# New_Project_2025-06-11_12-14-33.net
KiCad netlist of a schematic drawn in EasyEDA Pro
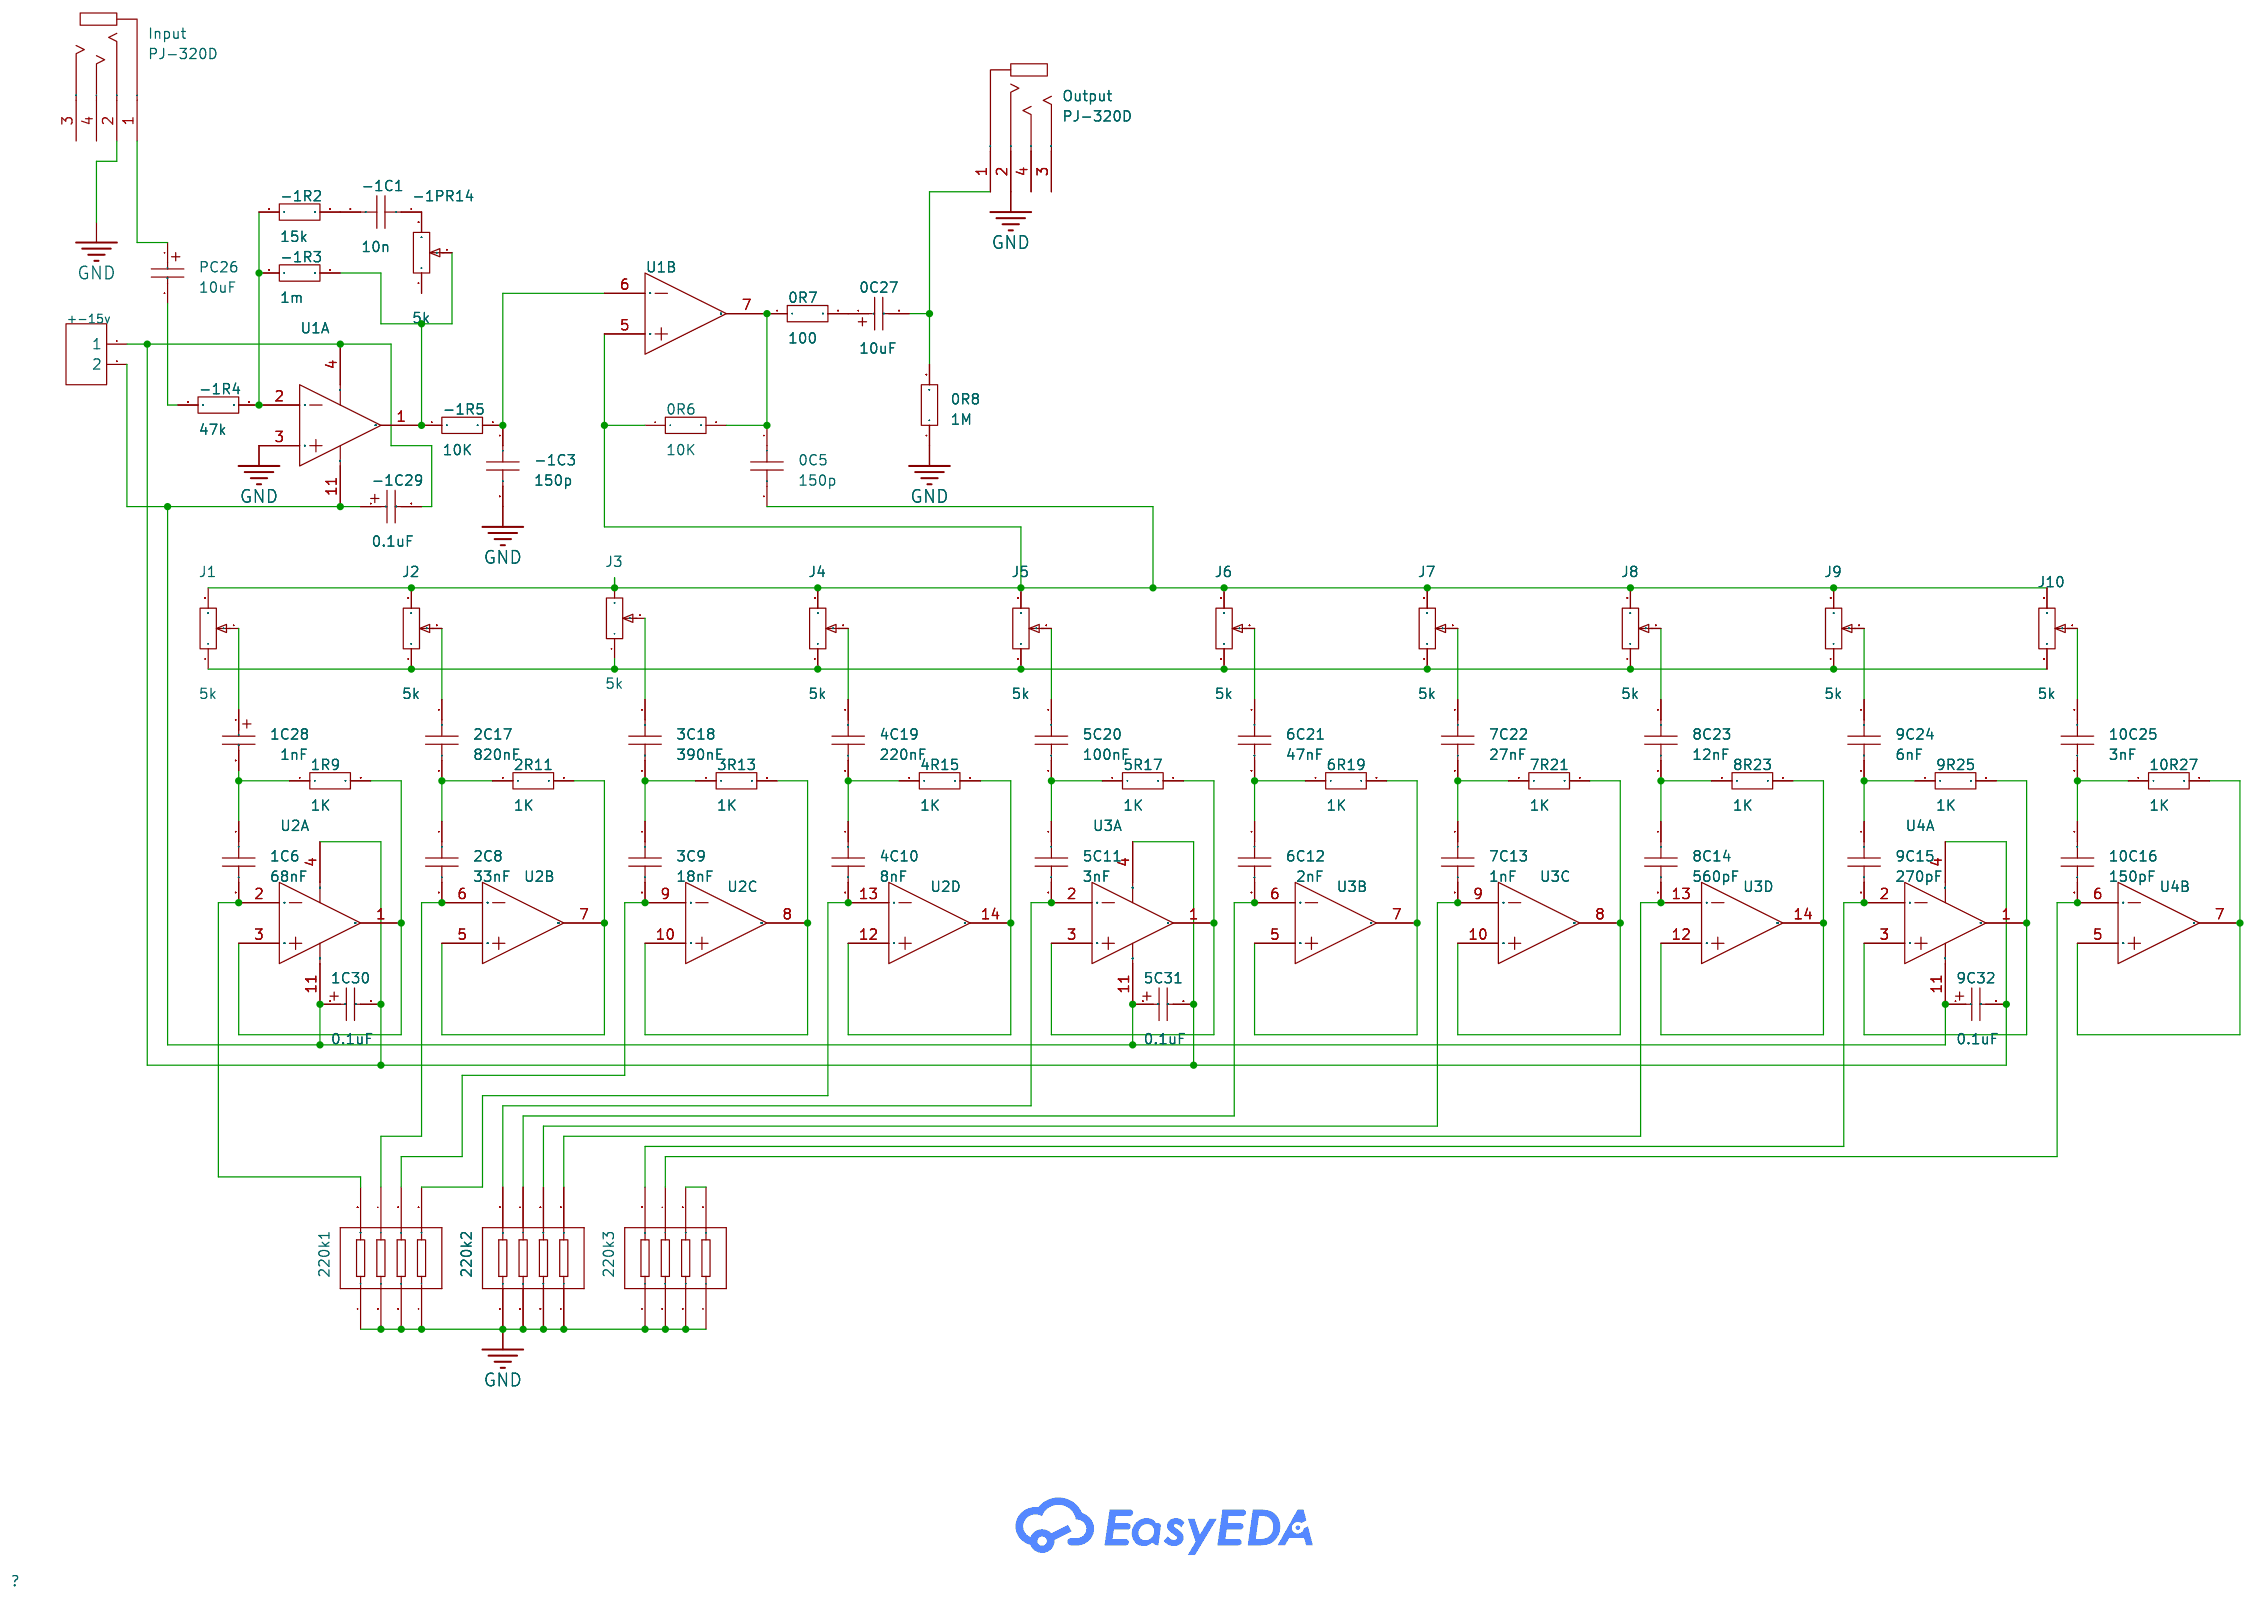
[diagram p0: schematic sheet]

(export (version "E")
  (design (tool "Eeschema 10.0.6"))
  (components
    (comp (ref "+-15v")
      (value "~")
      (footprint "easyedapro:HDR-TH_2P-P2.54-V-F")
      (libsource (lib "easyedapro") (part "Header-Female-2.54_1x2"))
    )
    (comp (ref "-1C1")
      (value "10n")
      (footprint "easyedapro:C0603")
      (libsource (lib "easyedapro") (part "CAP"))
    )
    (comp (ref "-1C3")
      (value "150p")
      (footprint "easyedapro:C0603")
      (libsource (lib "easyedapro") (part "CAP"))
    )
    (comp (ref "-1C29")
      (value "0.1uF")
      (footprint "easyedapro:CAP-SMD_BD3.0-L3.3-W3.3-RD")
      (libsource (lib "easyedapro") (part "C_Ele_SMD"))
    )
    (comp (ref "-1PR14")
      (value "5k")
      (footprint "easyedapro:RES-ADJ-TH_3P-L9.5-W9.5-P2.54-BR-BS")
      (libsource (lib "easyedapro") (part "3386P-1-103LF"))
    )
    (comp (ref "-1R2")
      (value "15k")
      (footprint "easyedapro:RES-TH_BD1.8-L3.2-P7.20-D0.4")
      (libsource (lib "easyedapro") (part "Res"))
    )
    (comp (ref "-1R3")
      (value "1m")
      (footprint "easyedapro:RES-TH_BD1.8-L3.2-P7.20-D0.4")
      (libsource (lib "easyedapro") (part "Res"))
    )
    (comp (ref "-1R4")
      (value "47k")
      (footprint "easyedapro:RES-TH_BD1.8-L3.2-P7.20-D0.4")
      (libsource (lib "easyedapro") (part "Res"))
    )
    (comp (ref "-1R5")
      (value "10K")
      (footprint "easyedapro:RES-TH_BD1.8-L3.2-P7.20-D0.4")
      (libsource (lib "easyedapro") (part "Res"))
    )
    (comp (ref "0C5")
      (value "150p")
      (footprint "easyedapro:C0603")
      (libsource (lib "easyedapro") (part "CAP"))
    )
    (comp (ref "0C27")
      (value "10uF")
      (footprint "easyedapro:CAP-SMD_BD3.0-L3.3-W3.3-RD")
      (libsource (lib "easyedapro") (part "C_Ele_SMD"))
    )
    (comp (ref "0R6")
      (value "10K")
      (footprint "easyedapro:RES-TH_BD1.8-L3.2-P7.20-D0.4")
      (libsource (lib "easyedapro") (part "Res"))
    )
    (comp (ref "0R7")
      (value "100")
      (footprint "easyedapro:RES-TH_BD1.8-L3.2-P7.20-D0.4")
      (libsource (lib "easyedapro") (part "Res"))
    )
    (comp (ref "0R8")
      (value "1M")
      (footprint "easyedapro:RES-TH_BD1.8-L3.2-P7.20-D0.4")
      (libsource (lib "easyedapro") (part "Res"))
    )
    (comp (ref "1C6")
      (value "68nF")
      (footprint "easyedapro:C0603")
      (libsource (lib "easyedapro") (part "CAP"))
    )
    (comp (ref "1C28")
      (value "1nF")
      (footprint "easyedapro:CAP-SMD_BD3.0-L3.3-W3.3-RD")
      (libsource (lib "easyedapro") (part "C_Ele_SMD"))
    )
    (comp (ref "1C30")
      (value "0.1uF")
      (footprint "easyedapro:CAP-SMD_BD3.0-L3.3-W3.3-RD")
      (libsource (lib "easyedapro") (part "C_Ele_SMD"))
    )
    (comp (ref "1R9")
      (value "1K")
      (footprint "easyedapro:RES-TH_BD1.8-L3.2-P7.20-D0.4")
      (libsource (lib "easyedapro") (part "Res"))
    )
    (comp (ref "2C8")
      (value "33nF")
      (footprint "easyedapro:C0603")
      (libsource (lib "easyedapro") (part "CAP"))
    )
    (comp (ref "2C17")
      (value "820nF")
      (footprint "easyedapro:C0603")
      (libsource (lib "easyedapro") (part "CAP"))
    )
    (comp (ref "2R11")
      (value "1K")
      (footprint "easyedapro:RES-TH_BD1.8-L3.2-P7.20-D0.4")
      (libsource (lib "easyedapro") (part "Res"))
    )
    (comp (ref "3C9")
      (value "18nF")
      (footprint "easyedapro:C0603")
      (libsource (lib "easyedapro") (part "CAP"))
    )
    (comp (ref "3C18")
      (value "390nF")
      (footprint "easyedapro:C0603")
      (libsource (lib "easyedapro") (part "CAP"))
    )
    (comp (ref "3R13")
      (value "1K")
      (footprint "easyedapro:RES-TH_BD1.8-L3.2-P7.20-D0.4")
      (libsource (lib "easyedapro") (part "Res"))
    )
    (comp (ref "4C10")
      (value "8nF")
      (footprint "easyedapro:C0603")
      (libsource (lib "easyedapro") (part "CAP"))
    )
    (comp (ref "4C19")
      (value "220nF")
      (footprint "easyedapro:C0603")
      (libsource (lib "easyedapro") (part "CAP"))
    )
    (comp (ref "4R15")
      (value "1K")
      (footprint "easyedapro:RES-TH_BD1.8-L3.2-P7.20-D0.4")
      (libsource (lib "easyedapro") (part "Res"))
    )
    (comp (ref "5C11")
      (value "3nF")
      (footprint "easyedapro:C0603")
      (libsource (lib "easyedapro") (part "CAP"))
    )
    (comp (ref "5C20")
      (value "100nF")
      (footprint "easyedapro:C0603")
      (libsource (lib "easyedapro") (part "CAP"))
    )
    (comp (ref "5C31")
      (value "0.1uF")
      (footprint "easyedapro:CAP-SMD_BD3.0-L3.3-W3.3-RD")
      (libsource (lib "easyedapro") (part "C_Ele_SMD"))
    )
    (comp (ref "5R17")
      (value "1K")
      (footprint "easyedapro:RES-TH_BD1.8-L3.2-P7.20-D0.4")
      (libsource (lib "easyedapro") (part "Res"))
    )
    (comp (ref "6C12")
      (value "2nF")
      (footprint "easyedapro:C0603")
      (libsource (lib "easyedapro") (part "CAP"))
    )
    (comp (ref "6C21")
      (value "47nF")
      (footprint "easyedapro:C0603")
      (libsource (lib "easyedapro") (part "CAP"))
    )
    (comp (ref "6R19")
      (value "1K")
      (footprint "easyedapro:RES-TH_BD1.8-L3.2-P7.20-D0.4")
      (libsource (lib "easyedapro") (part "Res"))
    )
    (comp (ref "7C13")
      (value "1nF")
      (footprint "easyedapro:C0603")
      (libsource (lib "easyedapro") (part "CAP"))
    )
    (comp (ref "7C22")
      (value "27nF")
      (footprint "easyedapro:C0603")
      (libsource (lib "easyedapro") (part "CAP"))
    )
    (comp (ref "7R21")
      (value "1K")
      (footprint "easyedapro:RES-TH_BD1.8-L3.2-P7.20-D0.4")
      (libsource (lib "easyedapro") (part "Res"))
    )
    (comp (ref "8C14")
      (value "560pF")
      (footprint "easyedapro:C0603")
      (libsource (lib "easyedapro") (part "CAP"))
    )
    (comp (ref "8C23")
      (value "12nF")
      (footprint "easyedapro:C0603")
      (libsource (lib "easyedapro") (part "CAP"))
    )
    (comp (ref "8R23")
      (value "1K")
      (footprint "easyedapro:RES-TH_BD1.8-L3.2-P7.20-D0.4")
      (libsource (lib "easyedapro") (part "Res"))
    )
    (comp (ref "9C15")
      (value "270pF")
      (footprint "easyedapro:C0603")
      (libsource (lib "easyedapro") (part "CAP"))
    )
    (comp (ref "9C24")
      (value "6nF")
      (footprint "easyedapro:C0603")
      (libsource (lib "easyedapro") (part "CAP"))
    )
    (comp (ref "9C32")
      (value "0.1uF")
      (footprint "easyedapro:CAP-SMD_BD3.0-L3.3-W3.3-RD")
      (libsource (lib "easyedapro") (part "C_Ele_SMD"))
    )
    (comp (ref "9R25")
      (value "1K")
      (footprint "easyedapro:RES-TH_BD1.8-L3.2-P7.20-D0.4")
      (libsource (lib "easyedapro") (part "Res"))
    )
    (comp (ref "10C16")
      (value "150pF")
      (footprint "easyedapro:C0603")
      (libsource (lib "easyedapro") (part "CAP"))
    )
    (comp (ref "10C25")
      (value "3nF")
      (footprint "easyedapro:C0603")
      (libsource (lib "easyedapro") (part "CAP"))
    )
    (comp (ref "10R27")
      (value "1K")
      (footprint "easyedapro:RES-TH_BD1.8-L3.2-P7.20-D0.4")
      (libsource (lib "easyedapro") (part "Res"))
    )
    (comp (ref "220k1")
      (value "220K")
      (footprint "easyedapro:RES-ARRAY-SMD_0603-8P-L3.2-W1.6-BL")
      (fields
        (field (name "Manufacturer Part") "4D03WGJ0221T5E")
        (field (name "Manufacturer") "UNI-ROYAL(厚声)")
      )
      (libsource (lib "easyedapro") (part "4D03WGJ0221T5E"))
    )
    (comp (ref "220k2")
      (value "220K")
      (footprint "easyedapro:RES-ARRAY-SMD_0603-8P-L3.2-W1.6-BL")
      (fields
        (field (name "Manufacturer Part") "4D03WGJ0221T5E")
        (field (name "Manufacturer") "UNI-ROYAL(厚声)")
      )
      (libsource (lib "easyedapro") (part "4D03WGJ0221T5E"))
    )
    (comp (ref "220k3")
      (value "220K")
      (footprint "easyedapro:RES-ARRAY-SMD_0603-8P-L3.2-W1.6-BL")
      (fields
        (field (name "Manufacturer Part") "4D03WGJ0221T5E")
        (field (name "Manufacturer") "UNI-ROYAL(厚声)")
      )
      (libsource (lib "easyedapro") (part "4D03WGJ0221T5E"))
    )
    (comp (ref "Input")
      (value "PJ-320D")
      (footprint "easyedapro:AUDIO-SMD_CIKI_PJ-320D_C2987375")
      (fields (field (name "Manufacturer") "CIKI(皓富)"))
      (libsource (lib "easyedapro") (part "PJ-320D_C2987375"))
    )
    (comp (ref "J1")
      (value "5k")
      (footprint "easyedapro:RES-ADJ-TH_3P-L9.5-W9.5-P2.54-BR-BS")
      (libsource (lib "easyedapro") (part "3386P-1-103LF"))
    )
    (comp (ref "J2")
      (value "5k")
      (footprint "easyedapro:RES-ADJ-TH_3P-L9.5-W9.5-P2.54-BR-BS")
      (libsource (lib "easyedapro") (part "3386P-1-103LF"))
    )
    (comp (ref "J3")
      (value "5k")
      (footprint "easyedapro:RES-ADJ-TH_3P-L9.5-W9.5-P2.54-BR-BS")
      (libsource (lib "easyedapro") (part "3386P-1-103LF"))
    )
    (comp (ref "J4")
      (value "5k")
      (footprint "easyedapro:RES-ADJ-TH_3P-L9.5-W9.5-P2.54-BR-BS")
      (libsource (lib "easyedapro") (part "3386P-1-103LF"))
    )
    (comp (ref "J5")
      (value "5k")
      (footprint "easyedapro:RES-ADJ-TH_3P-L9.5-W9.5-P2.54-BR-BS")
      (libsource (lib "easyedapro") (part "3386P-1-103LF"))
    )
    (comp (ref "J6")
      (value "5k")
      (footprint "easyedapro:RES-ADJ-TH_3P-L9.5-W9.5-P2.54-BR-BS")
      (libsource (lib "easyedapro") (part "3386P-1-103LF"))
    )
    (comp (ref "J7")
      (value "5k")
      (footprint "easyedapro:RES-ADJ-TH_3P-L9.5-W9.5-P2.54-BR-BS")
      (libsource (lib "easyedapro") (part "3386P-1-103LF"))
    )
    (comp (ref "J8")
      (value "5k")
      (footprint "easyedapro:RES-ADJ-TH_3P-L9.5-W9.5-P2.54-BR-BS")
      (libsource (lib "easyedapro") (part "3386P-1-103LF"))
    )
    (comp (ref "J9")
      (value "5k")
      (footprint "easyedapro:RES-ADJ-TH_3P-L9.5-W9.5-P2.54-BR-BS")
      (libsource (lib "easyedapro") (part "3386P-1-103LF"))
    )
    (comp (ref "J10")
      (value "5k")
      (footprint "easyedapro:RES-ADJ-TH_3P-L9.5-W9.5-P2.54-BR-BS")
      (libsource (lib "easyedapro") (part "3386P-1-103LF"))
    )
    (comp (ref "Output")
      (value "PJ-320D")
      (footprint "easyedapro:AUDIO-SMD_CIKI_PJ-320D_C2987375")
      (fields (field (name "Manufacturer") "CIKI(皓富)"))
      (libsource (lib "easyedapro") (part "PJ-320D_C2987375"))
    )
    (comp (ref "PC26")
      (value "10uF")
      (footprint "easyedapro:CAP-SMD_BD3.0-L3.3-W3.3-RD")
      (libsource (lib "easyedapro") (part "C_Ele_SMD"))
    )
    (comp (ref "U1")
      (value "~")
      (footprint "easyedapro:SOIC-14_L8.7-W3.9-P1.27-LS6.0-BL")
      (fields (field (name "Manufacturer Part") "TL074IDT") (field (name "Manufacturer") "ST(意法半导体)"))
      (libsource (lib "easyedapro") (part "TL074IDT"))
    )
    (comp (ref "U2")
      (value "~")
      (footprint "easyedapro:SOIC-14_L8.7-W3.9-P1.27-LS6.0-BL")
      (fields (field (name "Manufacturer Part") "TL074IDT") (field (name "Manufacturer") "ST(意法半导体)"))
      (libsource (lib "easyedapro") (part "TL074IDT"))
    )
    (comp (ref "U3")
      (value "~")
      (footprint "easyedapro:SOIC-14_L8.7-W3.9-P1.27-LS6.0-BL")
      (fields (field (name "Manufacturer Part") "TL074IDT") (field (name "Manufacturer") "ST(意法半导体)"))
      (libsource (lib "easyedapro") (part "TL074IDT"))
    )
    (comp (ref "U4")
      (value "~")
      (footprint "easyedapro:SOIC-14_L8.7-W3.9-P1.27-LS6.0-BL")
      (fields (field (name "Manufacturer Part") "TL074IDT") (field (name "Manufacturer") "ST(意法半导体)"))
      (libsource (lib "easyedapro") (part "TL074IDT"))
    )
  )
  (nets
    (net (code "1") (name "GND") (class "Default")
      (node (ref "-1C3") (pin "2") (pinfunction "2_2") (pintype "input"))
      (node (ref "0R8") (pin "1") (pinfunction "1_1") (pintype "input"))
      (node (ref "220k1") (pin "1") (pinfunction "1_1") (pintype "input"))
      (node (ref "220k1") (pin "2") (pinfunction "2_2") (pintype "input"))
      (node (ref "220k1") (pin "3") (pinfunction "3_3") (pintype "input"))
      (node (ref "220k1") (pin "4") (pinfunction "4_4") (pintype "input"))
      (node (ref "220k2") (pin "1") (pinfunction "1_1") (pintype "input"))
      (node (ref "220k2") (pin "2") (pinfunction "2_2") (pintype "input"))
      (node (ref "220k2") (pin "3") (pinfunction "3_3") (pintype "input"))
      (node (ref "220k2") (pin "4") (pinfunction "4_4") (pintype "input"))
      (node (ref "220k3") (pin "1") (pinfunction "1_1") (pintype "input"))
      (node (ref "220k3") (pin "2") (pinfunction "2_2") (pintype "input"))
      (node (ref "220k3") (pin "3") (pinfunction "3_3") (pintype "input"))
      (node (ref "220k3") (pin "4") (pinfunction "4_4") (pintype "input"))
      (node (ref "Input") (pin "2") (pinfunction "2_2") (pintype "unspecified"))
      (node (ref "Output") (pin "2") (pinfunction "2_2") (pintype "unspecified"))
      (node (ref "U1") (pin "3") (pinfunction "1IN+_3") (pintype "input"))
    )
    (net (code "2") (name "Net-(-1C1-Pad1)") (class "Default")
      (node (ref "-1C1") (pin "1") (pinfunction "1_1") (pintype "input"))
      (node (ref "-1PR14") (pin "3") (pinfunction "3_3") (pintype "input"))
    )
    (net (code "3") (name "Net-(-1C1-Pad2)") (class "Default")
      (node (ref "-1C1") (pin "2") (pinfunction "2_2") (pintype "input"))
      (node (ref "-1R2") (pin "2") (pinfunction "2_2") (pintype "input"))
    )
    (net (code "4") (name "Net-(-1R4-Pad1)") (class "Default")
      (node (ref "-1R4") (pin "1") (pinfunction "1_1") (pintype "input"))
      (node (ref "PC26") (pin "2") (pinfunction "2_2") (pintype "input"))
    )
    (net (code "5") (name "Net-(0C27-Pad1)") (class "Default")
      (node (ref "0C27") (pin "1") (pinfunction "1_1") (pintype "input"))
      (node (ref "0R7") (pin "2") (pinfunction "2_2") (pintype "input"))
    )
    (net (code "6") (name "Net-(0C27-Pad2)") (class "Default")
      (node (ref "0C27") (pin "2") (pinfunction "2_2") (pintype "input"))
      (node (ref "0R8") (pin "2") (pinfunction "2_2") (pintype "input"))
      (node (ref "Output") (pin "1") (pinfunction "1_1") (pintype "unspecified"))
    )
    (net (code "7") (name "Net-(1C28-Pad1)") (class "Default")
      (node (ref "1C28") (pin "1") (pinfunction "1_1") (pintype "input"))
      (node (ref "J1") (pin "2") (pinfunction "2_2") (pintype "input"))
    )
    (net (code "8") (name "Net-(1C28-Pad2)") (class "Default")
      (node (ref "1C28") (pin "2") (pinfunction "2_2") (pintype "input"))
      (node (ref "1C6") (pin "1") (pinfunction "1_1") (pintype "input"))
      (node (ref "1R9") (pin "1") (pinfunction "1_1") (pintype "input"))
    )
    (net (code "9") (name "Net-(2C17-Pad1)") (class "Default")
      (node (ref "2C17") (pin "1") (pinfunction "1_1") (pintype "input"))
      (node (ref "J2") (pin "2") (pinfunction "2_2") (pintype "input"))
    )
    (net (code "10") (name "Net-(2C17-Pad2)") (class "Default")
      (node (ref "2C17") (pin "2") (pinfunction "2_2") (pintype "input"))
      (node (ref "2C8") (pin "1") (pinfunction "1_1") (pintype "input"))
      (node (ref "2R11") (pin "1") (pinfunction "1_1") (pintype "input"))
    )
    (net (code "11") (name "Net-(3C18-Pad1)") (class "Default")
      (node (ref "3C18") (pin "1") (pinfunction "1_1") (pintype "input"))
      (node (ref "J3") (pin "2") (pinfunction "2_2") (pintype "input"))
    )
    (net (code "12") (name "Net-(3C18-Pad2)") (class "Default")
      (node (ref "3C18") (pin "2") (pinfunction "2_2") (pintype "input"))
      (node (ref "3C9") (pin "1") (pinfunction "1_1") (pintype "input"))
      (node (ref "3R13") (pin "1") (pinfunction "1_1") (pintype "input"))
    )
    (net (code "13") (name "Net-(4C10-Pad1)") (class "Default")
      (node (ref "4C10") (pin "1") (pinfunction "1_1") (pintype "input"))
      (node (ref "4C19") (pin "2") (pinfunction "2_2") (pintype "input"))
      (node (ref "4R15") (pin "1") (pinfunction "1_1") (pintype "input"))
    )
    (net (code "14") (name "Net-(4C19-Pad1)") (class "Default")
      (node (ref "4C19") (pin "1") (pinfunction "1_1") (pintype "input"))
      (node (ref "J4") (pin "2") (pinfunction "2_2") (pintype "input"))
    )
    (net (code "15") (name "Net-(5C11-Pad1)") (class "Default")
      (node (ref "5C11") (pin "1") (pinfunction "1_1") (pintype "input"))
      (node (ref "5C20") (pin "2") (pinfunction "2_2") (pintype "input"))
      (node (ref "5R17") (pin "1") (pinfunction "1_1") (pintype "input"))
    )
    (net (code "16") (name "Net-(5C20-Pad1)") (class "Default")
      (node (ref "5C20") (pin "1") (pinfunction "1_1") (pintype "input"))
      (node (ref "J5") (pin "2") (pinfunction "2_2") (pintype "input"))
    )
    (net (code "17") (name "Net-(6C12-Pad1)") (class "Default")
      (node (ref "6C12") (pin "1") (pinfunction "1_1") (pintype "input"))
      (node (ref "6C21") (pin "2") (pinfunction "2_2") (pintype "input"))
      (node (ref "6R19") (pin "1") (pinfunction "1_1") (pintype "input"))
    )
    (net (code "18") (name "Net-(6C21-Pad1)") (class "Default")
      (node (ref "6C21") (pin "1") (pinfunction "1_1") (pintype "input"))
      (node (ref "J6") (pin "2") (pinfunction "2_2") (pintype "input"))
    )
    (net (code "19") (name "Net-(7C13-Pad1)") (class "Default")
      (node (ref "7C13") (pin "1") (pinfunction "1_1") (pintype "input"))
      (node (ref "7C22") (pin "2") (pinfunction "2_2") (pintype "input"))
      (node (ref "7R21") (pin "1") (pinfunction "1_1") (pintype "input"))
    )
    (net (code "20") (name "Net-(7C22-Pad1)") (class "Default")
      (node (ref "7C22") (pin "1") (pinfunction "1_1") (pintype "input"))
      (node (ref "J7") (pin "2") (pinfunction "2_2") (pintype "input"))
    )
    (net (code "21") (name "Net-(8C14-Pad1)") (class "Default")
      (node (ref "8C14") (pin "1") (pinfunction "1_1") (pintype "input"))
      (node (ref "8C23") (pin "2") (pinfunction "2_2") (pintype "input"))
      (node (ref "8R23") (pin "1") (pinfunction "1_1") (pintype "input"))
    )
    (net (code "22") (name "Net-(8C23-Pad1)") (class "Default")
      (node (ref "8C23") (pin "1") (pinfunction "1_1") (pintype "input"))
      (node (ref "J8") (pin "2") (pinfunction "2_2") (pintype "input"))
    )
    (net (code "23") (name "Net-(9C15-Pad1)") (class "Default")
      (node (ref "9C15") (pin "1") (pinfunction "1_1") (pintype "input"))
      (node (ref "9C24") (pin "2") (pinfunction "2_2") (pintype "input"))
      (node (ref "9R25") (pin "1") (pinfunction "1_1") (pintype "input"))
    )
    (net (code "24") (name "Net-(9C24-Pad1)") (class "Default")
      (node (ref "9C24") (pin "1") (pinfunction "1_1") (pintype "input"))
      (node (ref "J9") (pin "2") (pinfunction "2_2") (pintype "input"))
    )
    (net (code "25") (name "Net-(10C16-Pad1)") (class "Default")
      (node (ref "10C16") (pin "1") (pinfunction "1_1") (pintype "input"))
      (node (ref "10C25") (pin "2") (pinfunction "2_2") (pintype "input"))
      (node (ref "10R27") (pin "1") (pinfunction "1_1") (pintype "input"))
    )
    (net (code "26") (name "Net-(10C25-Pad1)") (class "Default")
      (node (ref "10C25") (pin "1") (pinfunction "1_1") (pintype "input"))
      (node (ref "J10") (pin "2") (pinfunction "2_2") (pintype "input"))
    )
    (net (code "27") (name "Net-(220k3-Pad5)") (class "Default")
      (node (ref "220k3") (pin "5") (pinfunction "5_5") (pintype "input"))
      (node (ref "220k3") (pin "6") (pinfunction "6_6") (pintype "input"))
    )
    (net (code "28") (name "Net-(Input-Pad1)") (class "Default")
      (node (ref "Input") (pin "1") (pinfunction "1_1") (pintype "unspecified"))
      (node (ref "PC26") (pin "1") (pinfunction "1_1") (pintype "input"))
    )
    (net (code "29") (name "Net-(J1-Pad1)") (class "Default")
      (node (ref "J1") (pin "1") (pinfunction "1_1") (pintype "input"))
      (node (ref "J10") (pin "1") (pinfunction "1_1") (pintype "input"))
      (node (ref "J2") (pin "1") (pinfunction "1_1") (pintype "input"))
      (node (ref "J3") (pin "1") (pinfunction "1_1") (pintype "input"))
      (node (ref "J4") (pin "1") (pinfunction "1_1") (pintype "input"))
      (node (ref "J5") (pin "1") (pinfunction "1_1") (pintype "input"))
      (node (ref "J6") (pin "1") (pinfunction "1_1") (pintype "input"))
      (node (ref "J7") (pin "1") (pinfunction "1_1") (pintype "input"))
      (node (ref "J8") (pin "1") (pinfunction "1_1") (pintype "input"))
      (node (ref "J9") (pin "1") (pinfunction "1_1") (pintype "input"))
    )
    (net (code "30") (name "Net-(U1A-1IN-)") (class "Default")
      (node (ref "-1R2") (pin "1") (pinfunction "1_1") (pintype "input"))
      (node (ref "-1R3") (pin "1") (pinfunction "1_1") (pintype "input"))
      (node (ref "-1R4") (pin "2") (pinfunction "2_2") (pintype "input"))
      (node (ref "U1") (pin "2") (pinfunction "1IN-_2") (pintype "input"))
    )
    (net (code "31") (name "Net-(U1A-1OUT)") (class "Default")
      (node (ref "-1PR14") (pin "2") (pinfunction "2_2") (pintype "input"))
      (node (ref "-1R3") (pin "2") (pinfunction "2_2") (pintype "input"))
      (node (ref "-1R5") (pin "1") (pinfunction "1_1") (pintype "input"))
      (node (ref "U1") (pin "1") (pinfunction "1OUT_1") (pintype "input"))
    )
    (net (code "32") (name "Net-(U1A-VCC+)") (class "Default")
      (node (ref "+-15v") (pin "1") (pinfunction "1_1") (pintype "input"))
      (node (ref "-1C29") (pin "2") (pinfunction "2_2") (pintype "input"))
      (node (ref "1C30") (pin "2") (pinfunction "2_2") (pintype "input"))
      (node (ref "5C31") (pin "2") (pinfunction "2_2") (pintype "input"))
      (node (ref "9C32") (pin "2") (pinfunction "2_2") (pintype "input"))
      (node (ref "U1") (pin "4") (pinfunction "VCC+_4") (pintype "input"))
      (node (ref "U2") (pin "4") (pinfunction "VCC+_4") (pintype "input"))
      (node (ref "U3") (pin "4") (pinfunction "VCC+_4") (pintype "input"))
      (node (ref "U4") (pin "4") (pinfunction "VCC+_4") (pintype "input"))
    )
    (net (code "33") (name "Net-(U1A-VCC-)") (class "Default")
      (node (ref "+-15v") (pin "2") (pinfunction "2_2") (pintype "input"))
      (node (ref "-1C29") (pin "1") (pinfunction "1_1") (pintype "input"))
      (node (ref "1C30") (pin "1") (pinfunction "1_1") (pintype "input"))
      (node (ref "5C31") (pin "1") (pinfunction "1_1") (pintype "input"))
      (node (ref "9C32") (pin "1") (pinfunction "1_1") (pintype "input"))
      (node (ref "U1") (pin "11") (pinfunction "VCC-_11") (pintype "input"))
      (node (ref "U2") (pin "11") (pinfunction "VCC-_11") (pintype "input"))
      (node (ref "U3") (pin "11") (pinfunction "VCC-_11") (pintype "input"))
      (node (ref "U4") (pin "11") (pinfunction "VCC-_11") (pintype "input"))
    )
    (net (code "34") (name "Net-(U1B-2IN+)") (class "Default")
      (node (ref "0C5") (pin "2") (pinfunction "2_2") (pintype "input"))
      (node (ref "0R6") (pin "1") (pinfunction "1_1") (pintype "input"))
      (node (ref "J1") (pin "3") (pinfunction "3_3") (pintype "input"))
      (node (ref "J10") (pin "3") (pinfunction "3_3") (pintype "input"))
      (node (ref "J2") (pin "3") (pinfunction "3_3") (pintype "input"))
      (node (ref "J3") (pin "3") (pinfunction "3_3") (pintype "input"))
      (node (ref "J4") (pin "3") (pinfunction "3_3") (pintype "input"))
      (node (ref "J5") (pin "3") (pinfunction "3_3") (pintype "input"))
      (node (ref "J6") (pin "3") (pinfunction "3_3") (pintype "input"))
      (node (ref "J7") (pin "3") (pinfunction "3_3") (pintype "input"))
      (node (ref "J8") (pin "3") (pinfunction "3_3") (pintype "input"))
      (node (ref "J9") (pin "3") (pinfunction "3_3") (pintype "input"))
      (node (ref "U1") (pin "5") (pinfunction "2IN+_5") (pintype "input"))
    )
    (net (code "35") (name "Net-(U1B-2IN-)") (class "Default")
      (node (ref "-1C3") (pin "1") (pinfunction "1_1") (pintype "input"))
      (node (ref "-1R5") (pin "2") (pinfunction "2_2") (pintype "input"))
      (node (ref "U1") (pin "6") (pinfunction "2IN-_6") (pintype "input"))
    )
    (net (code "36") (name "Net-(U1B-2OUT)") (class "Default")
      (node (ref "0C5") (pin "1") (pinfunction "1_1") (pintype "input"))
      (node (ref "0R6") (pin "2") (pinfunction "2_2") (pintype "input"))
      (node (ref "0R7") (pin "1") (pinfunction "1_1") (pintype "input"))
      (node (ref "U1") (pin "7") (pinfunction "2OUT_7") (pintype "input"))
    )
    (net (code "37") (name "Net-(U2A-1IN+)") (class "Default")
      (node (ref "1R9") (pin "2") (pinfunction "2_2") (pintype "input"))
      (node (ref "U2") (pin "1") (pinfunction "1OUT_1") (pintype "input"))
      (node (ref "U2") (pin "3") (pinfunction "1IN+_3") (pintype "input"))
    )
    (net (code "38") (name "Net-(U2A-1IN-)") (class "Default")
      (node (ref "1C6") (pin "2") (pinfunction "2_2") (pintype "input"))
      (node (ref "220k1") (pin "8") (pinfunction "8_8") (pintype "input"))
      (node (ref "U2") (pin "2") (pinfunction "1IN-_2") (pintype "input"))
    )
    (net (code "39") (name "Net-(U2B-2IN+)") (class "Default")
      (node (ref "2R11") (pin "2") (pinfunction "2_2") (pintype "input"))
      (node (ref "U2") (pin "5") (pinfunction "2IN+_5") (pintype "input"))
      (node (ref "U2") (pin "7") (pinfunction "2OUT_7") (pintype "input"))
    )
    (net (code "40") (name "Net-(U2B-2IN-)") (class "Default")
      (node (ref "220k1") (pin "7") (pinfunction "7_7") (pintype "input"))
      (node (ref "2C8") (pin "2") (pinfunction "2_2") (pintype "input"))
      (node (ref "U2") (pin "6") (pinfunction "2IN-_6") (pintype "input"))
    )
    (net (code "41") (name "Net-(U2C-3IN+)") (class "Default")
      (node (ref "3R13") (pin "2") (pinfunction "2_2") (pintype "input"))
      (node (ref "U2") (pin "10") (pinfunction "3IN+_10") (pintype "input"))
      (node (ref "U2") (pin "8") (pinfunction "3OUT_8") (pintype "input"))
    )
    (net (code "42") (name "Net-(U2C-3IN-)") (class "Default")
      (node (ref "220k1") (pin "6") (pinfunction "6_6") (pintype "input"))
      (node (ref "3C9") (pin "2") (pinfunction "2_2") (pintype "input"))
      (node (ref "U2") (pin "9") (pinfunction "3IN-_9") (pintype "input"))
    )
    (net (code "43") (name "Net-(U2D-4IN+)") (class "Default")
      (node (ref "4R15") (pin "2") (pinfunction "2_2") (pintype "input"))
      (node (ref "U2") (pin "12") (pinfunction "4IN+_12") (pintype "input"))
      (node (ref "U2") (pin "14") (pinfunction "4OUT_14") (pintype "input"))
    )
    (net (code "44") (name "Net-(U2D-4IN-)") (class "Default")
      (node (ref "220k1") (pin "5") (pinfunction "5_5") (pintype "input"))
      (node (ref "4C10") (pin "2") (pinfunction "2_2") (pintype "input"))
      (node (ref "U2") (pin "13") (pinfunction "4IN-_13") (pintype "input"))
    )
    (net (code "45") (name "Net-(U3A-1IN+)") (class "Default")
      (node (ref "5R17") (pin "2") (pinfunction "2_2") (pintype "input"))
      (node (ref "U3") (pin "1") (pinfunction "1OUT_1") (pintype "input"))
      (node (ref "U3") (pin "3") (pinfunction "1IN+_3") (pintype "input"))
    )
    (net (code "46") (name "Net-(U3A-1IN-)") (class "Default")
      (node (ref "220k2") (pin "8") (pinfunction "8_8") (pintype "input"))
      (node (ref "5C11") (pin "2") (pinfunction "2_2") (pintype "input"))
      (node (ref "U3") (pin "2") (pinfunction "1IN-_2") (pintype "input"))
    )
    (net (code "47") (name "Net-(U3B-2IN+)") (class "Default")
      (node (ref "6R19") (pin "2") (pinfunction "2_2") (pintype "input"))
      (node (ref "U3") (pin "5") (pinfunction "2IN+_5") (pintype "input"))
      (node (ref "U3") (pin "7") (pinfunction "2OUT_7") (pintype "input"))
    )
    (net (code "48") (name "Net-(U3B-2IN-)") (class "Default")
      (node (ref "220k2") (pin "7") (pinfunction "7_7") (pintype "input"))
      (node (ref "6C12") (pin "2") (pinfunction "2_2") (pintype "input"))
      (node (ref "U3") (pin "6") (pinfunction "2IN-_6") (pintype "input"))
    )
    (net (code "49") (name "Net-(U3C-3IN+)") (class "Default")
      (node (ref "7R21") (pin "2") (pinfunction "2_2") (pintype "input"))
      (node (ref "U3") (pin "10") (pinfunction "3IN+_10") (pintype "input"))
      (node (ref "U3") (pin "8") (pinfunction "3OUT_8") (pintype "input"))
    )
    (net (code "50") (name "Net-(U3C-3IN-)") (class "Default")
      (node (ref "220k2") (pin "6") (pinfunction "6_6") (pintype "input"))
      (node (ref "7C13") (pin "2") (pinfunction "2_2") (pintype "input"))
      (node (ref "U3") (pin "9") (pinfunction "3IN-_9") (pintype "input"))
    )
    (net (code "51") (name "Net-(U3D-4IN+)") (class "Default")
      (node (ref "8R23") (pin "2") (pinfunction "2_2") (pintype "input"))
      (node (ref "U3") (pin "12") (pinfunction "4IN+_12") (pintype "input"))
      (node (ref "U3") (pin "14") (pinfunction "4OUT_14") (pintype "input"))
    )
    (net (code "52") (name "Net-(U3D-4IN-)") (class "Default")
      (node (ref "220k2") (pin "5") (pinfunction "5_5") (pintype "input"))
      (node (ref "8C14") (pin "2") (pinfunction "2_2") (pintype "input"))
      (node (ref "U3") (pin "13") (pinfunction "4IN-_13") (pintype "input"))
    )
    (net (code "53") (name "Net-(U4A-1IN+)") (class "Default")
      (node (ref "9R25") (pin "2") (pinfunction "2_2") (pintype "input"))
      (node (ref "U4") (pin "1") (pinfunction "1OUT_1") (pintype "input"))
      (node (ref "U4") (pin "3") (pinfunction "1IN+_3") (pintype "input"))
    )
    (net (code "54") (name "Net-(U4A-1IN-)") (class "Default")
      (node (ref "220k3") (pin "8") (pinfunction "8_8") (pintype "input"))
      (node (ref "9C15") (pin "2") (pinfunction "2_2") (pintype "input"))
      (node (ref "U4") (pin "2") (pinfunction "1IN-_2") (pintype "input"))
    )
    (net (code "55") (name "Net-(U4B-2IN+)") (class "Default")
      (node (ref "10R27") (pin "2") (pinfunction "2_2") (pintype "input"))
      (node (ref "U4") (pin "5") (pinfunction "2IN+_5") (pintype "input"))
      (node (ref "U4") (pin "7") (pinfunction "2OUT_7") (pintype "input"))
    )
    (net (code "56") (name "Net-(U4B-2IN-)") (class "Default")
      (node (ref "10C16") (pin "2") (pinfunction "2_2") (pintype "input"))
      (node (ref "220k3") (pin "7") (pinfunction "7_7") (pintype "input"))
      (node (ref "U4") (pin "6") (pinfunction "2IN-_6") (pintype "input"))
    )
    (net (code "57") (name "unconnected-(-1PR14-Pad1)") (class "Default")
      (node (ref "-1PR14") (pin "1") (pinfunction "1_1") (pintype "input"))
    )
    (net (code "58") (name "unconnected-(Input-Pad3)") (class "Default")
      (node (ref "Input") (pin "3") (pinfunction "3_3") (pintype "unspecified"))
    )
    (net (code "59") (name "unconnected-(Input-Pad4)") (class "Default")
      (node (ref "Input") (pin "4") (pinfunction "4_4") (pintype "unspecified"))
    )
    (net (code "60") (name "unconnected-(Output-Pad3)") (class "Default")
      (node (ref "Output") (pin "3") (pinfunction "3_3") (pintype "unspecified"))
    )
    (net (code "61") (name "unconnected-(Output-Pad4)") (class "Default")
      (node (ref "Output") (pin "4") (pinfunction "4_4") (pintype "unspecified"))
    )
  )
)
